# flux.net
KiCad netlist of a schematic drawn in EAGLE
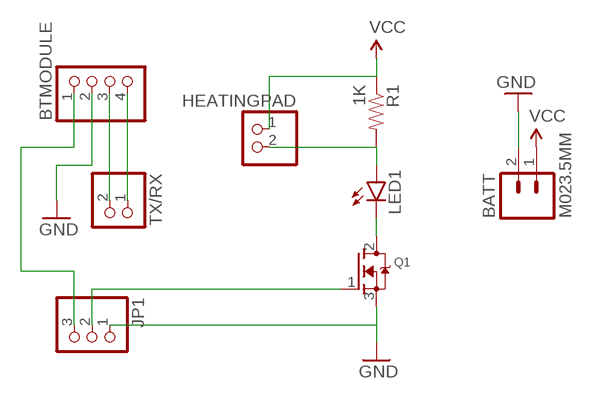
[diagram p0: schematic, sheet 1]

(export (version "E")
  (design (tool "Eeschema 10.0.6"))
  (components
    (comp (ref "BATT")
      (value "M023.5MM")
      (footprint "eagle-import:SCREWTERMINAL-3.5MM-2")
      (libsource (lib "eagle-import") (part "M023.5MM"))
    )
    (comp (ref "BTMODULE")
      (value "PINHD-1X4")
      (footprint "eagle-import:1X04")
      (libsource (lib "eagle-import") (part "PINHD-1X4"))
    )
    (comp (ref "HEATINGPAD")
      (value "PINHD-1X2")
      (footprint "eagle-import:1X02")
      (libsource (lib "eagle-import") (part "PINHD-1X2"))
    )
    (comp (ref "JP1")
      (value "PINHD-1X3")
      (footprint "eagle-import:1X03")
      (libsource (lib "eagle-import") (part "PINHD-1X3"))
    )
    (comp (ref "LED1")
      (value "LED3MM")
      (footprint "eagle-import:LED3MM")
      (libsource (lib "eagle-import") (part "LED3MM"))
    )
    (comp (ref "Q1")
      (value "MOSFET-NGDS_TO220V")
      (footprint "eagle-import:TO220V")
      (libsource (lib "eagle-import") (part "MOSFET-NGDS_TO220V"))
    )
    (comp (ref "R1")
      (value "1K")
      (footprint "eagle-import:AXIAL-0.3")
      (libsource (lib "eagle-import") (part "1KOHM-1/4W-1%(PTH)"))
    )
    (comp (ref "TX/RX")
      (value "PINHD-1X2")
      (footprint "eagle-import:1X02")
      (libsource (lib "eagle-import") (part "PINHD-1X2"))
    )
  )
  (nets
    (net (code "1") (name "GND") (class "Default")
      (node (ref "BATT") (pin "2") (pinfunction "2_2") (pintype "passive"))
      (node (ref "BTMODULE") (pin "2") (pinfunction "2_2") (pintype "passive"))
      (node (ref "JP1") (pin "1") (pinfunction "1_1") (pintype "passive"))
      (node (ref "Q1") (pin "3") (pinfunction "S_3") (pintype "bidirectional"))
    )
    (net (code "2") (name "Net-(BTMODULE-Pad1)") (class "Default")
      (node (ref "BTMODULE") (pin "1") (pinfunction "1_1") (pintype "passive"))
      (node (ref "JP1") (pin "3") (pinfunction "3_3") (pintype "passive"))
    )
    (net (code "3") (name "Net-(BTMODULE-Pad3)") (class "Default")
      (node (ref "BTMODULE") (pin "3") (pinfunction "3_3") (pintype "passive"))
      (node (ref "TX/RX") (pin "2") (pinfunction "2_2") (pintype "passive"))
    )
    (net (code "4") (name "Net-(BTMODULE-Pad4)") (class "Default")
      (node (ref "BTMODULE") (pin "4") (pinfunction "4_4") (pintype "passive"))
      (node (ref "TX/RX") (pin "1") (pinfunction "1_1") (pintype "passive"))
    )
    (net (code "5") (name "Net-(LED1-C)") (class "Default")
      (node (ref "LED1") (pin "K") (pinfunction "C_K") (pintype "passive"))
      (node (ref "Q1") (pin "2") (pinfunction "D_2") (pintype "bidirectional"))
    )
    (net (code "6") (name "Net-(Q1-G)") (class "Default")
      (node (ref "JP1") (pin "2") (pinfunction "2_2") (pintype "passive"))
      (node (ref "Q1") (pin "1") (pinfunction "G_1") (pintype "bidirectional"))
    )
    (net (code "7") (name "Net-(R1-2)") (class "Default")
      (node (ref "HEATINGPAD") (pin "2") (pinfunction "2_2") (pintype "passive"))
      (node (ref "LED1") (pin "A") (pinfunction "A_A") (pintype "passive"))
      (node (ref "R1") (pin "P$2") (pinfunction "2_P$2") (pintype "passive"))
    )
    (net (code "8") (name "VCC") (class "Default")
      (node (ref "BATT") (pin "1") (pinfunction "1_1") (pintype "passive"))
      (node (ref "HEATINGPAD") (pin "1") (pinfunction "1_1") (pintype "passive"))
      (node (ref "R1") (pin "P$1") (pinfunction "1_P$1") (pintype "passive"))
    )
  )
)
